# wifi-advent-wings.net
KiCad netlist of a schematic drawn in EAGLE
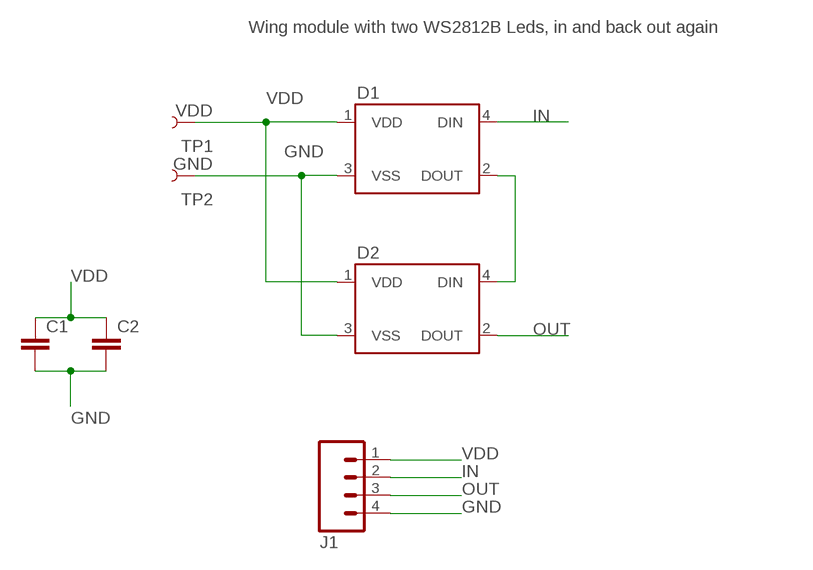
[diagram p0: schematic, sheet 1]

(export (version "E")
  (design (tool "Eeschema 10.0.6"))
  (components
    (comp (ref "C1")
      (value "CAP0805")
      (footprint "eagle-import:0805")
      (libsource (lib "eagle-import") (part "CAP0805"))
    )
    (comp (ref "C2")
      (value "CAP0805")
      (footprint "eagle-import:0805")
      (libsource (lib "eagle-import") (part "CAP0805"))
    )
    (comp (ref "D1")
      (value "WS2812B")
      (footprint "eagle-import:WS2812B")
      (libsource (lib "eagle-import") (part "WS2812B"))
    )
    (comp (ref "D2")
      (value "WS2812B")
      (footprint "eagle-import:WS2812B")
      (libsource (lib "eagle-import") (part "WS2812B"))
    )
    (comp (ref "J1")
      (value "M041X04_NO_SILK")
      (footprint "eagle-import:1X04_NO_SILK")
      (libsource (lib "eagle-import") (part "M041X04_NO_SILK"))
    )
    (comp (ref "TP1")
      (value "VDD")
      (footprint "eagle-import:PAD.03X.03")
      (libsource (lib "eagle-import") (part "TEST-POINT3"))
    )
    (comp (ref "TP2")
      (value "GND")
      (footprint "eagle-import:PAD.03X.03")
      (libsource (lib "eagle-import") (part "TEST-POINT3"))
    )
  )
  (nets
    (net (code "1") (name "/GND") (class "Default")
      (node (ref "C1") (pin "2") (pinfunction "2_2") (pintype "passive"))
      (node (ref "C2") (pin "2") (pinfunction "2_2") (pintype "passive"))
      (node (ref "D1") (pin "3") (pinfunction "VSS_3") (pintype "power_in"))
      (node (ref "D2") (pin "3") (pinfunction "VSS_3") (pintype "power_in"))
      (node (ref "J1") (pin "4") (pinfunction "4_4") (pintype "passive"))
      (node (ref "TP2") (pin "P$1") (pinfunction "1_P$1") (pintype "bidirectional"))
    )
    (net (code "2") (name "/IN") (class "Default")
      (node (ref "D1") (pin "4") (pinfunction "DIN_4") (pintype "input"))
      (node (ref "J1") (pin "2") (pinfunction "2_2") (pintype "passive"))
    )
    (net (code "3") (name "/OUT") (class "Default")
      (node (ref "D2") (pin "2") (pinfunction "DOUT_2") (pintype "output"))
      (node (ref "J1") (pin "3") (pinfunction "3_3") (pintype "passive"))
    )
    (net (code "4") (name "/VDD") (class "Default")
      (node (ref "C1") (pin "1") (pinfunction "1_1") (pintype "passive"))
      (node (ref "C2") (pin "1") (pinfunction "1_1") (pintype "passive"))
      (node (ref "D1") (pin "1") (pinfunction "VDD_1") (pintype "power_in"))
      (node (ref "D2") (pin "1") (pinfunction "VDD_1") (pintype "power_in"))
      (node (ref "J1") (pin "1") (pinfunction "1_1") (pintype "passive"))
      (node (ref "TP1") (pin "P$1") (pinfunction "1_P$1") (pintype "bidirectional"))
    )
    (net (code "5") (name "Net-(D1-DOUT)") (class "Default")
      (node (ref "D1") (pin "2") (pinfunction "DOUT_2") (pintype "output"))
      (node (ref "D2") (pin "4") (pinfunction "DIN_4") (pintype "input"))
    )
  )
)
